# search_controller.net
KiCad netlist of a schematic drawn in EAGLE
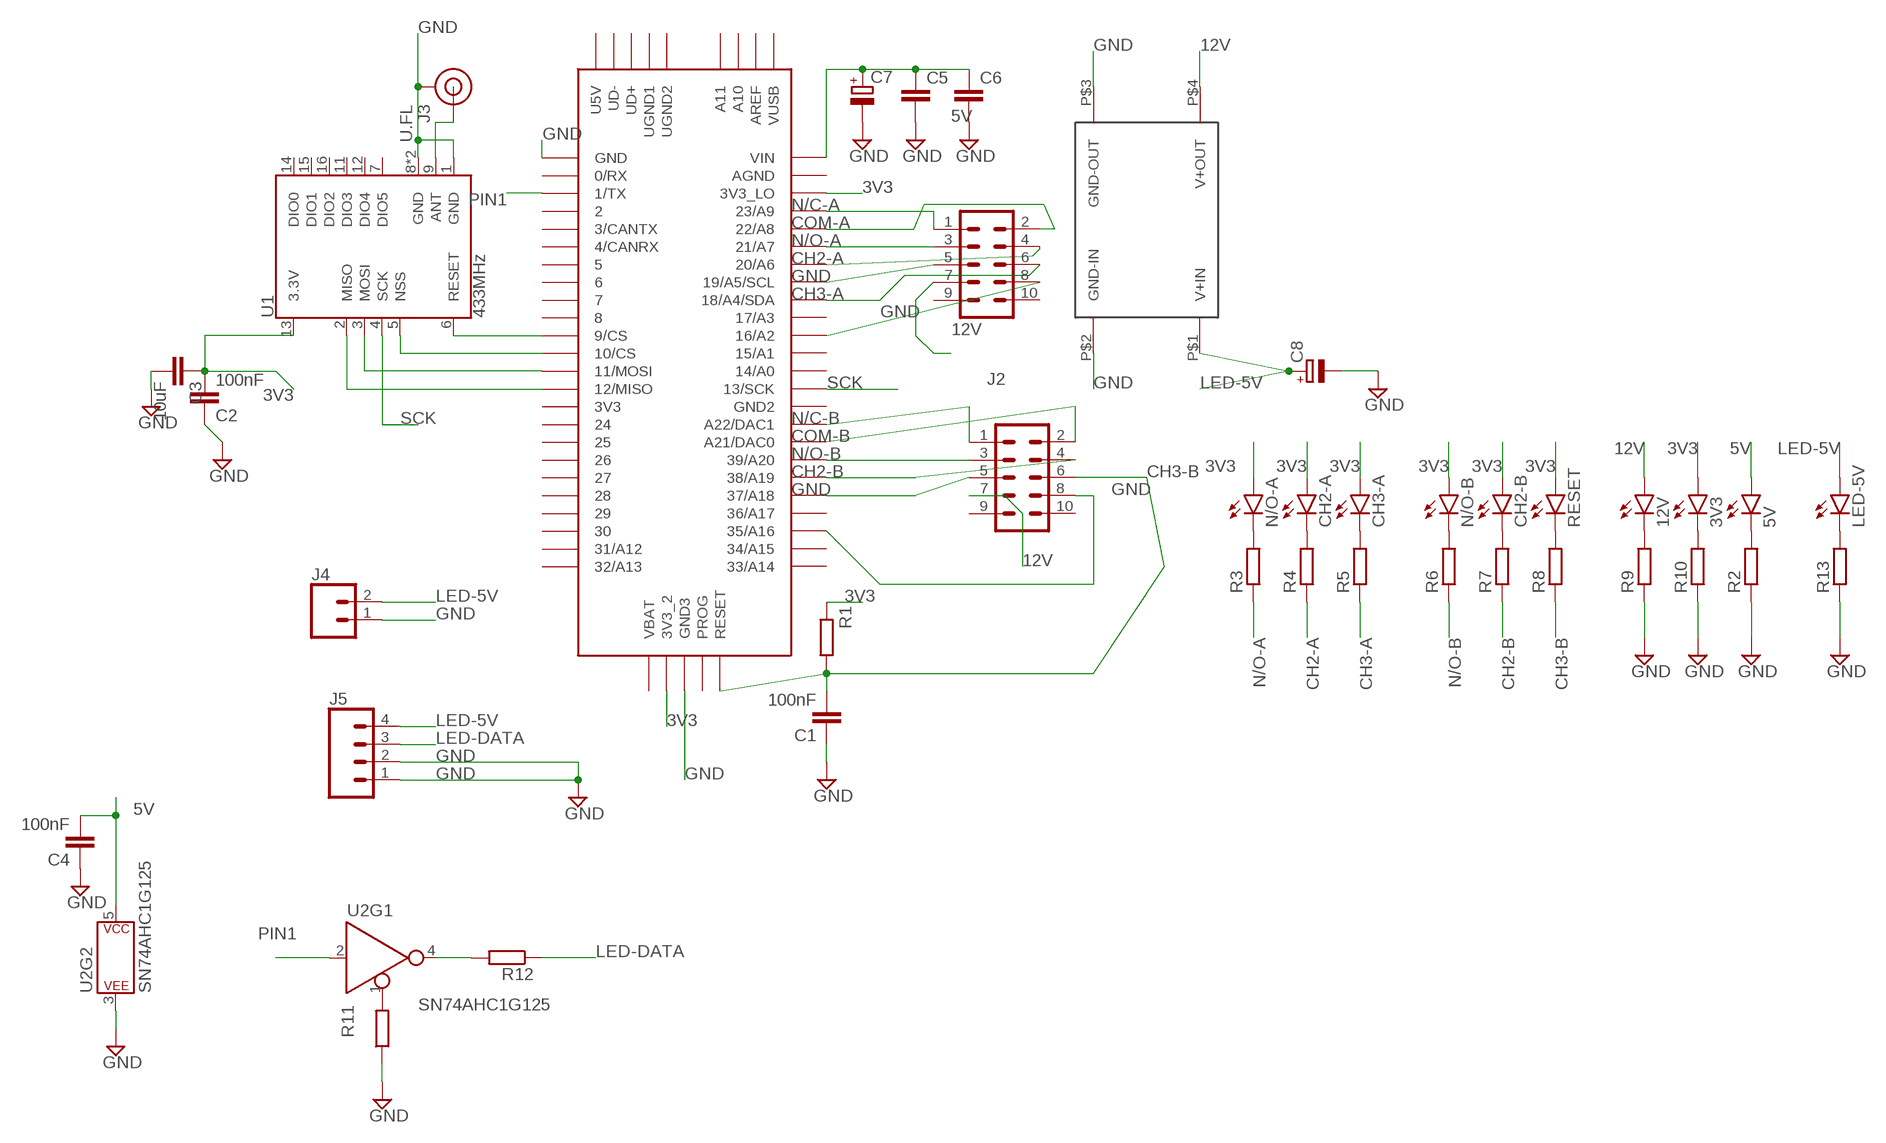
[diagram p0: schematic, sheet 1]

(export (version "E")
  (design (tool "Eeschema 10.0.6"))
  (components
    (comp (ref "3V3")
      (value "LEDCHIPLED_0805")
      (footprint "eagle-import:CHIPLED_0805")
      (libsource (lib "eagle-import") (part "LEDCHIPLED_0805"))
    )
    (comp (ref "5V")
      (value "LEDCHIPLED_0805")
      (footprint "eagle-import:CHIPLED_0805")
      (libsource (lib "eagle-import") (part "LEDCHIPLED_0805"))
    )
    (comp (ref "12V")
      (value "LEDCHIPLED_0805")
      (footprint "eagle-import:CHIPLED_0805")
      (libsource (lib "eagle-import") (part "LEDCHIPLED_0805"))
    )
    (comp (ref "C1")
      (value "100nF")
      (footprint "eagle-import:C0805")
      (libsource (lib "eagle-import") (part "C-EUC0805"))
    )
    (comp (ref "C2")
      (value "100nF")
      (footprint "eagle-import:C0805")
      (libsource (lib "eagle-import") (part "C-EUC0805"))
    )
    (comp (ref "C3")
      (value "10uF")
      (footprint "eagle-import:C0805")
      (libsource (lib "eagle-import") (part "C-EUC0805"))
    )
    (comp (ref "C4")
      (value "100nF")
      (footprint "eagle-import:C0805")
      (libsource (lib "eagle-import") (part "C-EUC0805"))
    )
    (comp (ref "C5")
      (value "C-EUC0805K")
      (footprint "eagle-import:C0805K")
      (libsource (lib "eagle-import") (part "C-EUC0805K"))
    )
    (comp (ref "C6")
      (value "C-EUC0805K")
      (footprint "eagle-import:C0805K")
      (libsource (lib "eagle-import") (part "C-EUC0805K"))
    )
    (comp (ref "C7")
      (value "CPOL-EUE2,5-6E")
      (footprint "eagle-import:E2,5-6E")
      (libsource (lib "eagle-import") (part "CPOL-EUE2,5-6E"))
    )
    (comp (ref "C8")
      (value "CPOL-EUE5-8.5")
      (footprint "eagle-import:E5-8,5")
      (libsource (lib "eagle-import") (part "CPOL-EUE5-8.5"))
    )
    (comp (ref "CH2-A")
      (value "LEDCHIPLED_0805")
      (footprint "eagle-import:CHIPLED_0805")
      (libsource (lib "eagle-import") (part "LEDCHIPLED_0805"))
    )
    (comp (ref "CH2-B")
      (value "LEDCHIPLED_0805")
      (footprint "eagle-import:CHIPLED_0805")
      (libsource (lib "eagle-import") (part "LEDCHIPLED_0805"))
    )
    (comp (ref "CH3-A")
      (value "LEDCHIPLED_0805")
      (footprint "eagle-import:CHIPLED_0805")
      (libsource (lib "eagle-import") (part "LEDCHIPLED_0805"))
    )
    (comp (ref "J1")
      (value "CONN_05X2PTH")
      (footprint "eagle-import:2X5")
      (libsource (lib "eagle-import") (part "CONN_05X2PTH"))
    )
    (comp (ref "J2")
      (value "CONN_05X2PTH")
      (footprint "eagle-import:2X5")
      (libsource (lib "eagle-import") (part "CONN_05X2PTH"))
    )
    (comp (ref "J3")
      (value "U.FL")
      (footprint "eagle-import:U.FL")
      (libsource (lib "eagle-import") (part "U.FL2PIN"))
    )
    (comp (ref "J4")
      (value "CONN_023.5MM-NO_SILK")
      (footprint "eagle-import:SCREWTERMINAL-3.5MM-2-NS")
      (libsource (lib "eagle-import") (part "CONN_023.5MM-NO_SILK"))
    )
    (comp (ref "J5")
      (value "CONN_04")
      (footprint "eagle-import:1X04")
      (libsource (lib "eagle-import") (part "CONN_04"))
    )
    (comp (ref "LED-5V")
      (value "LEDCHIPLED_0805")
      (footprint "eagle-import:CHIPLED_0805")
      (libsource (lib "eagle-import") (part "LEDCHIPLED_0805"))
    )
    (comp (ref "N/O-A")
      (value "LEDCHIPLED_0805")
      (footprint "eagle-import:CHIPLED_0805")
      (libsource (lib "eagle-import") (part "LEDCHIPLED_0805"))
    )
    (comp (ref "N/O-B")
      (value "LEDCHIPLED_0805")
      (footprint "eagle-import:CHIPLED_0805")
      (libsource (lib "eagle-import") (part "LEDCHIPLED_0805"))
    )
    (comp (ref "R1")
      (value "R-EU_M0805")
      (footprint "eagle-import:M0805")
      (libsource (lib "eagle-import") (part "R-EU_M0805"))
    )
    (comp (ref "R2")
      (value "R-EU_R0603")
      (footprint "eagle-import:R0603")
      (libsource (lib "eagle-import") (part "R-EU_R0603"))
    )
    (comp (ref "R3")
      (value "R-EU_R0603")
      (footprint "eagle-import:R0603")
      (libsource (lib "eagle-import") (part "R-EU_R0603"))
    )
    (comp (ref "R4")
      (value "R-EU_R0603")
      (footprint "eagle-import:R0603")
      (libsource (lib "eagle-import") (part "R-EU_R0603"))
    )
    (comp (ref "R5")
      (value "R-EU_R0603")
      (footprint "eagle-import:R0603")
      (libsource (lib "eagle-import") (part "R-EU_R0603"))
    )
    (comp (ref "R6")
      (value "R-EU_R0603")
      (footprint "eagle-import:R0603")
      (libsource (lib "eagle-import") (part "R-EU_R0603"))
    )
    (comp (ref "R7")
      (value "R-EU_R0603")
      (footprint "eagle-import:R0603")
      (libsource (lib "eagle-import") (part "R-EU_R0603"))
    )
    (comp (ref "R8")
      (value "R-EU_R0603")
      (footprint "eagle-import:R0603")
      (libsource (lib "eagle-import") (part "R-EU_R0603"))
    )
    (comp (ref "R9")
      (value "R-EU_R0603")
      (footprint "eagle-import:R0603")
      (libsource (lib "eagle-import") (part "R-EU_R0603"))
    )
    (comp (ref "R10")
      (value "R-EU_R0603")
      (footprint "eagle-import:R0603")
      (libsource (lib "eagle-import") (part "R-EU_R0603"))
    )
    (comp (ref "R11")
      (value "R-EU_R0603")
      (footprint "eagle-import:R0603")
      (libsource (lib "eagle-import") (part "R-EU_R0603"))
    )
    (comp (ref "R12")
      (value "R-EU_R0603")
      (footprint "eagle-import:R0603")
      (libsource (lib "eagle-import") (part "R-EU_R0603"))
    )
    (comp (ref "R13")
      (value "R-EU_R0603")
      (footprint "eagle-import:R0603")
      (libsource (lib "eagle-import") (part "R-EU_R0603"))
    )
    (comp (ref "RESET")
      (value "LEDCHIPLED_0805")
      (footprint "eagle-import:CHIPLED_0805")
      (libsource (lib "eagle-import") (part "LEDCHIPLED_0805"))
    )
    (comp (ref "U$1")
      (value "TEENSY_3.5/3.6")
      (footprint "eagle-import:TEENSY_3.5_3.6")
      (libsource (lib "eagle-import") (part "TEENSY_3.5/3.6"))
    )
    (comp (ref "U$2")
      (value "BUCK/BOOST")
      (footprint "eagle-import:STANDARDBUCKBOOST")
      (libsource (lib "eagle-import") (part "BUCK/BOOST"))
    )
    (comp (ref "U1")
      (value "433MHz")
      (footprint "eagle-import:RFM69HCW-XXXS2")
      (libsource (lib "eagle-import") (part "RFM69HCW-433"))
    )
    (comp (ref "U2")
      (value "SN74AHC1G125")
      (footprint "eagle-import:SOT23-5")
      (libsource (lib "eagle-import") (part "741G125DAHC"))
    )
  )
  (nets
    (net (code "1") (name "/3V3") (class "Default")
      (node (ref "3V3") (pin "A") (pinfunction "A_A") (pintype "passive"))
      (node (ref "C2") (pin "2") (pinfunction "2_2") (pintype "passive"))
      (node (ref "C3") (pin "1") (pinfunction "1_1") (pintype "passive"))
      (node (ref "CH2-A") (pin "A") (pinfunction "A_A") (pintype "passive"))
      (node (ref "CH2-B") (pin "A") (pinfunction "A_A") (pintype "passive"))
      (node (ref "CH3-A") (pin "A") (pinfunction "A_A") (pintype "passive"))
      (node (ref "N/O-A") (pin "A") (pinfunction "A_A") (pintype "passive"))
      (node (ref "N/O-B") (pin "A") (pinfunction "A_A") (pintype "passive"))
      (node (ref "R1") (pin "2") (pinfunction "2_2") (pintype "passive"))
      (node (ref "RESET") (pin "A") (pinfunction "A_A") (pintype "passive"))
      (node (ref "U$1") (pin "3V3_2") (pinfunction "3V3_2_3V3_2") (pintype "bidirectional"))
      (node (ref "U$1") (pin "3V3_LO") (pinfunction "3V3_LO_3V3_LO") (pintype "bidirectional"))
      (node (ref "U1") (pin "13") (pinfunction "3.3V_13") (pintype "power_in"))
    )
    (net (code "2") (name "/5V") (class "Default")
      (node (ref "5V") (pin "A") (pinfunction "A_A") (pintype "passive"))
      (node (ref "C4") (pin "2") (pinfunction "2_2") (pintype "passive"))
      (node (ref "C5") (pin "1") (pinfunction "1_1") (pintype "passive"))
      (node (ref "C6") (pin "1") (pinfunction "1_1") (pintype "passive"))
      (node (ref "C7") (pin "+") (pinfunction "+_+") (pintype "passive"))
      (node (ref "U$1") (pin "VIN") (pinfunction "VIN_VIN") (pintype "bidirectional"))
      (node (ref "U2") (pin "5") (pinfunction "P$V+_5") (pintype "bidirectional"))
    )
    (net (code "3") (name "/12V") (class "Default")
      (node (ref "12V") (pin "A") (pinfunction "A_A") (pintype "passive"))
      (node (ref "J1") (pin "7") (pinfunction "7_7") (pintype "passive"))
      (node (ref "J2") (pin "7") (pinfunction "7_7") (pintype "passive"))
      (node (ref "U$2") (pin "P$4") (pinfunction "V+OUT_P$4") (pintype "bidirectional"))
    )
    (net (code "4") (name "/CH2-A") (class "Default")
      (node (ref "J1") (pin "4") (pinfunction "4_4") (pintype "passive"))
      (node (ref "R4") (pin "1") (pinfunction "1_1") (pintype "passive"))
      (node (ref "U$1") (pin "20/A6") (pinfunction "20/A6_20/A6") (pintype "bidirectional"))
    )
    (net (code "5") (name "/CH2-B") (class "Default")
      (node (ref "J2") (pin "4") (pinfunction "4_4") (pintype "passive"))
      (node (ref "R7") (pin "1") (pinfunction "1_1") (pintype "passive"))
      (node (ref "U$1") (pin "38/A19") (pinfunction "38/A19_38/A19") (pintype "bidirectional"))
    )
    (net (code "6") (name "/CH3-A") (class "Default")
      (node (ref "J1") (pin "6") (pinfunction "6_6") (pintype "passive"))
      (node (ref "R5") (pin "1") (pinfunction "1_1") (pintype "passive"))
      (node (ref "U$1") (pin "18/A4/SDA") (pinfunction "18/A4/SDA_18/A4/SDA") (pintype "bidirectional"))
    )
    (net (code "7") (name "/CH3-B") (class "Default")
      (node (ref "C1") (pin "2") (pinfunction "2_2") (pintype "passive"))
      (node (ref "J2") (pin "6") (pinfunction "6_6") (pintype "passive"))
      (node (ref "R1") (pin "1") (pinfunction "1_1") (pintype "passive"))
      (node (ref "R8") (pin "1") (pinfunction "1_1") (pintype "passive"))
      (node (ref "U$1") (pin "RESET") (pinfunction "RESET_RESET") (pintype "bidirectional"))
    )
    (net (code "8") (name "/COM-A") (class "Default")
      (node (ref "J1") (pin "2") (pinfunction "2_2") (pintype "passive"))
      (node (ref "U$1") (pin "22/A8") (pinfunction "22/A8_22/A8") (pintype "bidirectional"))
    )
    (net (code "9") (name "/COM-B") (class "Default")
      (node (ref "J2") (pin "2") (pinfunction "2_2") (pintype "passive"))
      (node (ref "U$1") (pin "21/DAC0") (pinfunction "A21/DAC0_21/DAC0") (pintype "bidirectional"))
    )
    (net (code "10") (name "/LED-5V") (class "Default")
      (node (ref "C8") (pin "+") (pinfunction "+_+") (pintype "passive"))
      (node (ref "J4") (pin "2") (pinfunction "2_2") (pintype "passive"))
      (node (ref "J5") (pin "4") (pinfunction "4_4") (pintype "passive"))
      (node (ref "LED-5V") (pin "A") (pinfunction "A_A") (pintype "passive"))
      (node (ref "U$2") (pin "P$1") (pinfunction "V+IN_P$1") (pintype "bidirectional"))
    )
    (net (code "11") (name "/LED-DATA") (class "Default")
      (node (ref "J5") (pin "3") (pinfunction "3_3") (pintype "passive"))
      (node (ref "R12") (pin "1") (pinfunction "1_1") (pintype "passive"))
    )
    (net (code "12") (name "/N{slash}C-A") (class "Default")
      (node (ref "J1") (pin "1") (pinfunction "1_1") (pintype "passive"))
      (node (ref "U$1") (pin "23/A9") (pinfunction "23/A9_23/A9") (pintype "bidirectional"))
    )
    (net (code "13") (name "/N{slash}C-B") (class "Default")
      (node (ref "J2") (pin "1") (pinfunction "1_1") (pintype "passive"))
      (node (ref "U$1") (pin "A22/DAC1") (pinfunction "A22/DAC1_A22/DAC1") (pintype "bidirectional"))
    )
    (net (code "14") (name "/N{slash}O-A") (class "Default")
      (node (ref "J1") (pin "3") (pinfunction "3_3") (pintype "passive"))
      (node (ref "R3") (pin "1") (pinfunction "1_1") (pintype "passive"))
      (node (ref "U$1") (pin "21/A7") (pinfunction "21/A7_21/A7") (pintype "bidirectional"))
    )
    (net (code "15") (name "/N{slash}O-B") (class "Default")
      (node (ref "J2") (pin "3") (pinfunction "3_3") (pintype "passive"))
      (node (ref "R6") (pin "1") (pinfunction "1_1") (pintype "passive"))
      (node (ref "U$1") (pin "39/A20") (pinfunction "39/A20_39/A20") (pintype "bidirectional"))
    )
    (net (code "16") (name "/PIN1") (class "Default")
      (node (ref "U$1") (pin "1/TX") (pinfunction "1/TX_1/TX") (pintype "bidirectional"))
      (node (ref "U2") (pin "2") (pinfunction "A_2") (pintype "bidirectional"))
    )
    (net (code "17") (name "/SCK") (class "Default")
      (node (ref "U$1") (pin "13/SCK") (pinfunction "13/SCK_13/SCK") (pintype "bidirectional"))
      (node (ref "U1") (pin "4") (pinfunction "SCK_4") (pintype "input"))
    )
    (net (code "18") (name "GND") (class "Default")
      (node (ref "C1") (pin "1") (pinfunction "1_1") (pintype "passive"))
      (node (ref "C2") (pin "1") (pinfunction "1_1") (pintype "passive"))
      (node (ref "C3") (pin "2") (pinfunction "2_2") (pintype "passive"))
      (node (ref "C4") (pin "1") (pinfunction "1_1") (pintype "passive"))
      (node (ref "C5") (pin "2") (pinfunction "2_2") (pintype "passive"))
      (node (ref "C6") (pin "2") (pinfunction "2_2") (pintype "passive"))
      (node (ref "C7") (pin "-") (pinfunction "-_-") (pintype "passive"))
      (node (ref "C8") (pin "-") (pinfunction "-_-") (pintype "passive"))
      (node (ref "J1") (pin "5") (pinfunction "5_5") (pintype "passive"))
      (node (ref "J1") (pin "8") (pinfunction "8_8") (pintype "passive"))
      (node (ref "J2") (pin "5") (pinfunction "5_5") (pintype "passive"))
      (node (ref "J2") (pin "8") (pinfunction "8_8") (pintype "passive"))
      (node (ref "J3") (pin "1") (pinfunction "GND_1") (pintype "bidirectional"))
      (node (ref "J3") (pin "2") (pinfunction "GND_2") (pintype "bidirectional"))
      (node (ref "J4") (pin "1") (pinfunction "1_1") (pintype "passive"))
      (node (ref "J5") (pin "1") (pinfunction "1_1") (pintype "passive"))
      (node (ref "J5") (pin "2") (pinfunction "2_2") (pintype "passive"))
      (node (ref "R10") (pin "1") (pinfunction "1_1") (pintype "passive"))
      (node (ref "R11") (pin "1") (pinfunction "1_1") (pintype "passive"))
      (node (ref "R13") (pin "1") (pinfunction "1_1") (pintype "passive"))
      (node (ref "R2") (pin "1") (pinfunction "1_1") (pintype "passive"))
      (node (ref "R9") (pin "1") (pinfunction "1_1") (pintype "passive"))
      (node (ref "U$1") (pin "16/A2") (pinfunction "16/A2_16/A2") (pintype "bidirectional"))
      (node (ref "U$1") (pin "19/A5/SCL") (pinfunction "19/A5/SCL_19/A5/SCL") (pintype "bidirectional"))
      (node (ref "U$1") (pin "35/A16") (pinfunction "35/A16_35/A16") (pintype "bidirectional"))
      (node (ref "U$1") (pin "37/A18") (pinfunction "37/A18_37/A18") (pintype "bidirectional"))
      (node (ref "U$1") (pin "GND") (pinfunction "GND_GND") (pintype "bidirectional"))
      (node (ref "U$1") (pin "GND3") (pinfunction "GND3_GND3") (pintype "bidirectional"))
      (node (ref "U$2") (pin "P$2") (pinfunction "GND-IN_P$2") (pintype "bidirectional"))
      (node (ref "U$2") (pin "P$3") (pinfunction "GND-OUT_P$3") (pintype "bidirectional"))
      (node (ref "U1") (pin "1") (pinfunction "GND_1") (pintype "power_in"))
      (node (ref "U1") (pin "10") (pinfunction "GND_10") (pintype "power_in"))
      (node (ref "U1") (pin "8") (pinfunction "GND_8") (pintype "power_in"))
      (node (ref "U2") (pin "3") (pinfunction "P$V-_3") (pintype "bidirectional"))
    )
    (net (code "19") (name "Net-(3V3-PadC)") (class "Default")
      (node (ref "3V3") (pin "C") (pinfunction "C_C") (pintype "passive"))
      (node (ref "R10") (pin "2") (pinfunction "2_2") (pintype "passive"))
    )
    (net (code "20") (name "Net-(5V-PadC)") (class "Default")
      (node (ref "5V") (pin "C") (pinfunction "C_C") (pintype "passive"))
      (node (ref "R2") (pin "2") (pinfunction "2_2") (pintype "passive"))
    )
    (net (code "21") (name "Net-(12V-PadC)") (class "Default")
      (node (ref "12V") (pin "C") (pinfunction "C_C") (pintype "passive"))
      (node (ref "R9") (pin "2") (pinfunction "2_2") (pintype "passive"))
    )
    (net (code "22") (name "Net-(CH2-A-PadC)") (class "Default")
      (node (ref "CH2-A") (pin "C") (pinfunction "C_C") (pintype "passive"))
      (node (ref "R4") (pin "2") (pinfunction "2_2") (pintype "passive"))
    )
    (net (code "23") (name "Net-(CH2-B-PadC)") (class "Default")
      (node (ref "CH2-B") (pin "C") (pinfunction "C_C") (pintype "passive"))
      (node (ref "R7") (pin "2") (pinfunction "2_2") (pintype "passive"))
    )
    (net (code "24") (name "Net-(CH3-A-PadC)") (class "Default")
      (node (ref "CH3-A") (pin "C") (pinfunction "C_C") (pintype "passive"))
      (node (ref "R5") (pin "2") (pinfunction "2_2") (pintype "passive"))
    )
    (net (code "25") (name "Net-(J3-SIGNAL)") (class "Default")
      (node (ref "J3") (pin "FEED") (pinfunction "SIGNAL_FEED") (pintype "bidirectional"))
      (node (ref "U1") (pin "9") (pinfunction "ANT_9") (pintype "passive"))
    )
    (net (code "26") (name "Net-(LED-5V-PadC)") (class "Default")
      (node (ref "LED-5V") (pin "C") (pinfunction "C_C") (pintype "passive"))
      (node (ref "R13") (pin "2") (pinfunction "2_2") (pintype "passive"))
    )
    (net (code "27") (name "Net-(N/O-A-PadC)") (class "Default")
      (node (ref "N/O-A") (pin "C") (pinfunction "C_C") (pintype "passive"))
      (node (ref "R3") (pin "2") (pinfunction "2_2") (pintype "passive"))
    )
    (net (code "28") (name "Net-(N/O-B-PadC)") (class "Default")
      (node (ref "N/O-B") (pin "C") (pinfunction "C_C") (pintype "passive"))
      (node (ref "R6") (pin "2") (pinfunction "2_2") (pintype "passive"))
    )
    (net (code "29") (name "Net-(R8-Pad2)") (class "Default")
      (node (ref "R8") (pin "2") (pinfunction "2_2") (pintype "passive"))
      (node (ref "RESET") (pin "C") (pinfunction "C_C") (pintype "passive"))
    )
    (net (code "30") (name "Net-(U1-MISO)") (class "Default")
      (node (ref "U$1") (pin "12/MISO") (pinfunction "12/MISO_12/MISO") (pintype "bidirectional"))
      (node (ref "U1") (pin "2") (pinfunction "MISO_2") (pintype "bidirectional"))
    )
    (net (code "31") (name "Net-(U1-MOSI)") (class "Default")
      (node (ref "U$1") (pin "11/MOSI") (pinfunction "11/MOSI_11/MOSI") (pintype "bidirectional"))
      (node (ref "U1") (pin "3") (pinfunction "MOSI_3") (pintype "input"))
    )
    (net (code "32") (name "Net-(U1-NSS)") (class "Default")
      (node (ref "U$1") (pin "10/CS") (pinfunction "10/CS_10/CS") (pintype "bidirectional"))
      (node (ref "U1") (pin "5") (pinfunction "NSS_5") (pintype "input"))
    )
    (net (code "33") (name "Net-(U1-RESET)") (class "Default")
      (node (ref "U$1") (pin "9/CS") (pinfunction "9/CS_9/CS") (pintype "bidirectional"))
      (node (ref "U1") (pin "6") (pinfunction "RESET_6") (pintype "input"))
    )
    (net (code "34") (name "Net-(U2A-Y)") (class "Default")
      (node (ref "R12") (pin "2") (pinfunction "2_2") (pintype "passive"))
      (node (ref "U2") (pin "4") (pinfunction "Y_4") (pintype "bidirectional"))
    )
    (net (code "35") (name "Net-(U2A-~{EN})") (class "Default")
      (node (ref "R11") (pin "2") (pinfunction "2_2") (pintype "passive"))
      (node (ref "U2") (pin "1") (pinfunction "~{EN}_1") (pintype "bidirectional"))
    )
    (net (code "36") (name "unconnected-(J1-Pad9)") (class "Default")
      (node (ref "J1") (pin "9") (pinfunction "9_9") (pintype "passive"))
    )
    (net (code "37") (name "unconnected-(J1-Pad10)") (class "Default")
      (node (ref "J1") (pin "10") (pinfunction "10_10") (pintype "passive"))
    )
    (net (code "38") (name "unconnected-(J2-Pad9)") (class "Default")
      (node (ref "J2") (pin "9") (pinfunction "9_9") (pintype "passive"))
    )
    (net (code "39") (name "unconnected-(J2-Pad10)") (class "Default")
      (node (ref "J2") (pin "10") (pinfunction "10_10") (pintype "passive"))
    )
    (net (code "40") (name "unconnected-(U$1-Pad0{slash}RX)") (class "Default")
      (node (ref "U$1") (pin "0/RX") (pinfunction "0/RX_0/RX") (pintype "bidirectional"))
    )
    (net (code "41") (name "unconnected-(U$1-Pad2)") (class "Default")
      (node (ref "U$1") (pin "2") (pinfunction "2_2") (pintype "bidirectional"))
    )
    (net (code "42") (name "unconnected-(U$1-Pad3V3)") (class "Default")
      (node (ref "U$1") (pin "3V3") (pinfunction "3V3_3V3") (pintype "bidirectional"))
    )
    (net (code "43") (name "unconnected-(U$1-Pad3{slash}CANTX)") (class "Default")
      (node (ref "U$1") (pin "3/CANTX") (pinfunction "3/CANTX_3/CANTX") (pintype "bidirectional"))
    )
    (net (code "44") (name "unconnected-(U$1-Pad4{slash}CANRX)") (class "Default")
      (node (ref "U$1") (pin "4/CANRX") (pinfunction "4/CANRX_4/CANRX") (pintype "bidirectional"))
    )
    (net (code "45") (name "unconnected-(U$1-Pad5)") (class "Default")
      (node (ref "U$1") (pin "5") (pinfunction "5_5") (pintype "bidirectional"))
    )
    (net (code "46") (name "unconnected-(U$1-Pad6)") (class "Default")
      (node (ref "U$1") (pin "6") (pinfunction "6_6") (pintype "bidirectional"))
    )
    (net (code "47") (name "unconnected-(U$1-Pad7)") (class "Default")
      (node (ref "U$1") (pin "7") (pinfunction "7_7") (pintype "bidirectional"))
    )
    (net (code "48") (name "unconnected-(U$1-Pad8)") (class "Default")
      (node (ref "U$1") (pin "8") (pinfunction "8_8") (pintype "bidirectional"))
    )
    (net (code "49") (name "unconnected-(U$1-Pad14{slash}A0)") (class "Default")
      (node (ref "U$1") (pin "14/A0") (pinfunction "14/A0_14/A0") (pintype "bidirectional"))
    )
    (net (code "50") (name "unconnected-(U$1-Pad15{slash}A1)") (class "Default")
      (node (ref "U$1") (pin "15/A1") (pinfunction "15/A1_15/A1") (pintype "bidirectional"))
    )
    (net (code "51") (name "unconnected-(U$1-Pad17{slash}A3)") (class "Default")
      (node (ref "U$1") (pin "17/A3") (pinfunction "17/A3_17/A3") (pintype "bidirectional"))
    )
    (net (code "52") (name "unconnected-(U$1-Pad24)") (class "Default")
      (node (ref "U$1") (pin "24") (pinfunction "24_24") (pintype "bidirectional"))
    )
    (net (code "53") (name "unconnected-(U$1-Pad25)") (class "Default")
      (node (ref "U$1") (pin "25") (pinfunction "25_25") (pintype "bidirectional"))
    )
    (net (code "54") (name "unconnected-(U$1-Pad26)") (class "Default")
      (node (ref "U$1") (pin "26") (pinfunction "26_26") (pintype "bidirectional"))
    )
    (net (code "55") (name "unconnected-(U$1-Pad27)") (class "Default")
      (node (ref "U$1") (pin "27") (pinfunction "27_27") (pintype "bidirectional"))
    )
    (net (code "56") (name "unconnected-(U$1-Pad28)") (class "Default")
      (node (ref "U$1") (pin "28") (pinfunction "28_28") (pintype "bidirectional"))
    )
    (net (code "57") (name "unconnected-(U$1-Pad29)") (class "Default")
      (node (ref "U$1") (pin "29") (pinfunction "29_29") (pintype "bidirectional"))
    )
    (net (code "58") (name "unconnected-(U$1-Pad30)") (class "Default")
      (node (ref "U$1") (pin "30") (pinfunction "30_30") (pintype "bidirectional"))
    )
    (net (code "59") (name "unconnected-(U$1-Pad31{slash}A12)") (class "Default")
      (node (ref "U$1") (pin "31/A12") (pinfunction "31/A12_31/A12") (pintype "bidirectional"))
    )
    (net (code "60") (name "unconnected-(U$1-Pad32{slash}A13)") (class "Default")
      (node (ref "U$1") (pin "32/A13") (pinfunction "32/A13_32/A13") (pintype "bidirectional"))
    )
    (net (code "61") (name "unconnected-(U$1-Pad33{slash}A14)") (class "Default")
      (node (ref "U$1") (pin "33/A14") (pinfunction "33/A14_33/A14") (pintype "bidirectional"))
    )
    (net (code "62") (name "unconnected-(U$1-Pad34{slash}A15)") (class "Default")
      (node (ref "U$1") (pin "34/A15") (pinfunction "34/A15_34/A15") (pintype "bidirectional"))
    )
    (net (code "63") (name "unconnected-(U$1-Pad36{slash}A17)") (class "Default")
      (node (ref "U$1") (pin "36/A17") (pinfunction "36/A17_36/A17") (pintype "bidirectional"))
    )
    (net (code "64") (name "unconnected-(U$1-PadA10)") (class "Default")
      (node (ref "U$1") (pin "A10") (pinfunction "A10_A10") (pintype "bidirectional"))
    )
    (net (code "65") (name "unconnected-(U$1-PadA11)") (class "Default")
      (node (ref "U$1") (pin "A11") (pinfunction "A11_A11") (pintype "bidirectional"))
    )
    (net (code "66") (name "unconnected-(U$1-PadAGND)") (class "Default")
      (node (ref "U$1") (pin "AGND") (pinfunction "AGND_AGND") (pintype "bidirectional"))
    )
    (net (code "67") (name "unconnected-(U$1-PadAREF)") (class "Default")
      (node (ref "U$1") (pin "AREF") (pinfunction "AREF_AREF") (pintype "bidirectional"))
    )
    (net (code "68") (name "unconnected-(U$1-PadGND2)") (class "Default")
      (node (ref "U$1") (pin "GND2") (pinfunction "GND2_GND2") (pintype "bidirectional"))
    )
    (net (code "69") (name "unconnected-(U$1-PadPROG)") (class "Default")
      (node (ref "U$1") (pin "PROG") (pinfunction "PROG_PROG") (pintype "bidirectional"))
    )
    (net (code "70") (name "unconnected-(U$1-PadU5V)") (class "Default")
      (node (ref "U$1") (pin "U5V") (pinfunction "U5V_U5V") (pintype "bidirectional"))
    )
    (net (code "71") (name "unconnected-(U$1-PadUD+)") (class "Default")
      (node (ref "U$1") (pin "UD+") (pinfunction "UD+_UD+") (pintype "bidirectional"))
    )
    (net (code "72") (name "unconnected-(U$1-PadUD-)") (class "Default")
      (node (ref "U$1") (pin "UD-") (pinfunction "UD-_UD-") (pintype "bidirectional"))
    )
    (net (code "73") (name "unconnected-(U$1-PadUGND1)") (class "Default")
      (node (ref "U$1") (pin "UGND1") (pinfunction "UGND1_UGND1") (pintype "bidirectional"))
    )
    (net (code "74") (name "unconnected-(U$1-PadUGND2)") (class "Default")
      (node (ref "U$1") (pin "UGND2") (pinfunction "UGND2_UGND2") (pintype "bidirectional"))
    )
    (net (code "75") (name "unconnected-(U$1-PadVBAT)") (class "Default")
      (node (ref "U$1") (pin "VBAT") (pinfunction "VBAT_VBAT") (pintype "bidirectional"))
    )
    (net (code "76") (name "unconnected-(U$1-PadVUSB)") (class "Default")
      (node (ref "U$1") (pin "VUSB") (pinfunction "VUSB_VUSB") (pintype "bidirectional"))
    )
    (net (code "77") (name "unconnected-(U1-DIO0-Pad14)") (class "Default")
      (node (ref "U1") (pin "14") (pinfunction "DIO0_14") (pintype "bidirectional"))
    )
    (net (code "78") (name "unconnected-(U1-DIO1-Pad15)") (class "Default")
      (node (ref "U1") (pin "15") (pinfunction "DIO1_15") (pintype "bidirectional"))
    )
    (net (code "79") (name "unconnected-(U1-DIO2-Pad16)") (class "Default")
      (node (ref "U1") (pin "16") (pinfunction "DIO2_16") (pintype "bidirectional"))
    )
    (net (code "80") (name "unconnected-(U1-DIO3-Pad11)") (class "Default")
      (node (ref "U1") (pin "11") (pinfunction "DIO3_11") (pintype "bidirectional"))
    )
    (net (code "81") (name "unconnected-(U1-DIO4-Pad12)") (class "Default")
      (node (ref "U1") (pin "12") (pinfunction "DIO4_12") (pintype "bidirectional"))
    )
    (net (code "82") (name "unconnected-(U1-DIO5-Pad7)") (class "Default")
      (node (ref "U1") (pin "7") (pinfunction "DIO5_7") (pintype "bidirectional"))
    )
  )
)
